# v1_2.net
KiCad netlist of a schematic drawn in Altium Designer
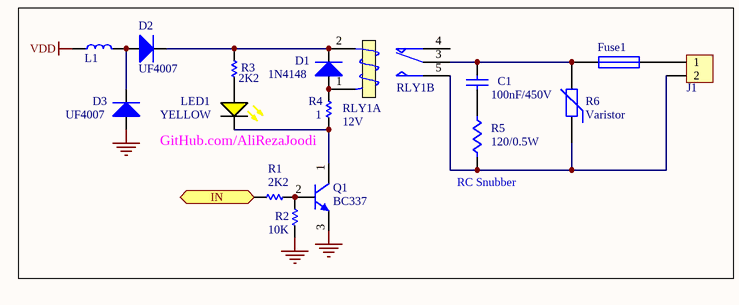
[diagram p0: v1.2.SchDoc]

(export (version "E")
  (design (tool "Eeschema 10.0.6"))
  (components
    (comp (ref "C1")
      (value "100nF/450V")
      (footprint "C_THD_CER_(P2.54-D3.5-T1.5)")
      (description "Capacitor, Ceramic Multilayer")
      (libsource (lib "Passive") (part "Capacitor_Ceramic"))
    )
    (comp (ref "D1")
      (value "1N4148")
      (footprint "DIODE0.4_Glass")
      (description "Default Diode")
      (fields (field (name "MANUFACTURER") "Generic Components") (field (name "PUBLISHER") "Altium Limited"))
      (libsource (lib "Miscellaneous Devices") (part "Diode"))
    )
    (comp (ref "D2")
      (value "UF4007")
      (footprint "D_THD_AXIAL0.4_DO-41")
      (description "Diode,")
      (libsource (lib "Passive") (part "Diode"))
    )
    (comp (ref "D3")
      (value "UF4007")
      (footprint "D_THD_AXIAL0.4_DO-41")
      (description "Diode,")
      (libsource (lib "Passive") (part "Diode"))
    )
    (comp (ref "Fuse1")
      (value "2A")
      (footprint "PIN-W2/E2.8")
      (description "Fuse")
      (fields (field (name "MANUFACTURER") "Generic Components") (field (name "PUBLISHER") "Altium Limited"))
      (libsource (lib "Miscellaneous Devices") (part "Fuse 1"))
    )
    (comp (ref "J1")
      (value "2PIN")
      (footprint "Connector_Phoenix_2PIN_MSTB")
      (description "Connector, Header, 2Pin")
      (libsource (lib "Connector") (part "Connector_Header_2Pin"))
    )
    (comp (ref "L1")
      (value "~")
      (description "Inductor,")
      (libsource (lib "Passive") (part "Inductor_2Type"))
    )
    (comp (ref "LED1")
      (value "YELLOW")
      (footprint "LED_THD_3MM_YELLOW_R")
      (description "LED, Yellow")
      (fields (field (name "MANUFACTURER") "Generic Components") (field (name "PUBLISHER") "Altium Limited"))
      (libsource (lib "Display") (part "LED_YELLOW"))
    )
    (comp (ref "Q1")
      (value "BC337")
      (footprint "TO92C")
      (description "NPN Bipolar Transistor")
      (fields (field (name "MANUFACTURER") "Generic Components") (field (name "PUBLISHER") "Altium Limited"))
      (libsource (lib "Miscellaneous Devices") (part "NPN"))
    )
    (comp (ref "R1")
      (value "2K2")
      (footprint "R_THD_AXIAL0.4(1/4W)")
      (description "Resistor")
      (libsource (lib "Passive") (part "Resistor"))
    )
    (comp (ref "R2")
      (value "10K")
      (footprint "R_THD_AXIAL0.4(1/4W)")
      (description "Resistor")
      (libsource (lib "Passive") (part "Resistor"))
    )
    (comp (ref "R3")
      (value "2K2")
      (footprint "R_THD_AXIAL0.4(1/4W)")
      (description "Resistor")
      (libsource (lib "Passive") (part "Resistor"))
    )
    (comp (ref "R4")
      (value "1")
      (footprint "R_THD_AXIAL0.4(1/4W)")
      (description "Resistor")
      (libsource (lib "Passive") (part "Resistor"))
    )
    (comp (ref "R5")
      (value "120/0.5W")
      (footprint "R_THD_AXIAL0.4(1/4W)")
      (description "Resistor")
      (libsource (lib "Passive") (part "Resistor_3Form"))
    )
    (comp (ref "R6")
      (value "Varistor")
      (footprint "R2012-0805")
      (description "Varistor (Voltage-Sensitive Resistor)")
      (fields (field (name "MANUFACTURER") "Generic Components") (field (name "PUBLISHER") "Altium Limited"))
      (libsource (lib "Miscellaneous Devices") (part "Res Varistor"))
    )
    (comp (ref "RLY1")
      (value "12V")
      (footprint "RELAY_SPDT_5PIN_2216")
      (description "SPDT Relay")
      (libsource (lib "Passive") (part "Relay_SPDT_2Form"))
    )
  )
  (nets
    (net (code "1") (name "/IN") (class "Default")
      (node (ref "R1") (pin "2") (pinfunction "2_2") (pintype "passive"))
    )
    (net (code "2") (name "GND") (class "Default")
      (node (ref "D3") (pin "1") (pinfunction "A_1") (pintype "passive"))
      (node (ref "Q1") (pin "3") (pinfunction "E_3") (pintype "passive"))
      (node (ref "R2") (pin "1") (pinfunction "1_1") (pintype "passive"))
    )
    (net (code "3") (name "Net-(C1-Pad1)") (class "Default")
      (node (ref "C1") (pin "1") (pinfunction "1_1") (pintype "passive"))
      (node (ref "R5") (pin "2") (pinfunction "2_2") (pintype "passive"))
    )
    (net (code "4") (name "Net-(D1-A)") (class "Default")
      (node (ref "D1") (pin "1") (pinfunction "A_1") (pintype "passive"))
      (node (ref "R4") (pin "2") (pinfunction "2_2") (pintype "passive"))
      (node (ref "RLY1") (pin "1") (pinfunction "T2_1") (pintype "passive"))
    )
    (net (code "5") (name "Net-(D1-K)") (class "Default")
      (node (ref "D1") (pin "2") (pinfunction "K_2") (pintype "passive"))
      (node (ref "D2") (pin "2") (pinfunction "K_2") (pintype "passive"))
      (node (ref "R3") (pin "2") (pinfunction "2_2") (pintype "passive"))
      (node (ref "RLY1") (pin "2") (pinfunction "T1_2") (pintype "passive"))
    )
    (net (code "6") (name "Net-(D2-A)") (class "Default")
      (node (ref "D2") (pin "1") (pinfunction "A_1") (pintype "passive"))
      (node (ref "D3") (pin "2") (pinfunction "K_2") (pintype "passive"))
      (node (ref "L1") (pin "2") (pinfunction "2_2") (pintype "passive"))
    )
    (net (code "7") (name "Net-(Fuse1-Pad2)") (class "Default")
      (node (ref "Fuse1") (pin "2") (pinfunction "2_2") (pintype "passive"))
      (node (ref "J1") (pin "1") (pinfunction "1_1") (pintype "passive"))
    )
    (net (code "8") (name "Net-(LED1-A)") (class "Default")
      (node (ref "LED1") (pin "1") (pinfunction "A_1") (pintype "passive"))
      (node (ref "R3") (pin "1") (pinfunction "1_1") (pintype "passive"))
    )
    (net (code "9") (name "Net-(LED1-K)") (class "Default")
      (node (ref "LED1") (pin "2") (pinfunction "K_2") (pintype "passive"))
      (node (ref "Q1") (pin "1") (pinfunction "C_1") (pintype "passive"))
      (node (ref "R4") (pin "1") (pinfunction "1_1") (pintype "passive"))
    )
    (net (code "10") (name "Net-(Q1-B)") (class "Default")
      (node (ref "Q1") (pin "2") (pinfunction "B_2") (pintype "passive"))
      (node (ref "R1") (pin "1") (pinfunction "1_1") (pintype "passive"))
      (node (ref "R2") (pin "2") (pinfunction "2_2") (pintype "passive"))
    )
    (net (code "11") (name "Net-(RLY1B-COM)") (class "Default")
      (node (ref "C1") (pin "2") (pinfunction "2_2") (pintype "passive"))
      (node (ref "Fuse1") (pin "1") (pinfunction "1_1") (pintype "passive"))
      (node (ref "R6") (pin "2") (pinfunction "2_2") (pintype "passive"))
      (node (ref "RLY1") (pin "3") (pinfunction "COM_3") (pintype "passive"))
    )
    (net (code "12") (name "Net-(RLY1B-NO)") (class "Default")
      (node (ref "J1") (pin "2") (pinfunction "2_2") (pintype "passive"))
      (node (ref "R5") (pin "1") (pinfunction "1_1") (pintype "passive"))
      (node (ref "R6") (pin "1") (pinfunction "1_1") (pintype "passive"))
      (node (ref "RLY1") (pin "5") (pinfunction "NO_5") (pintype "passive"))
    )
    (net (code "13") (name "VDD") (class "Default")
      (node (ref "L1") (pin "1") (pinfunction "1_1") (pintype "passive"))
    )
    (net (code "14") (name "unconnected-(RLY1B-NC-Pad4)") (class "Default")
      (node (ref "RLY1") (pin "4") (pinfunction "NC_4") (pintype "passive"))
    )
  )
)
